# CH32V007F8U6.net
KiCad netlist of a schematic drawn in Altium Designer
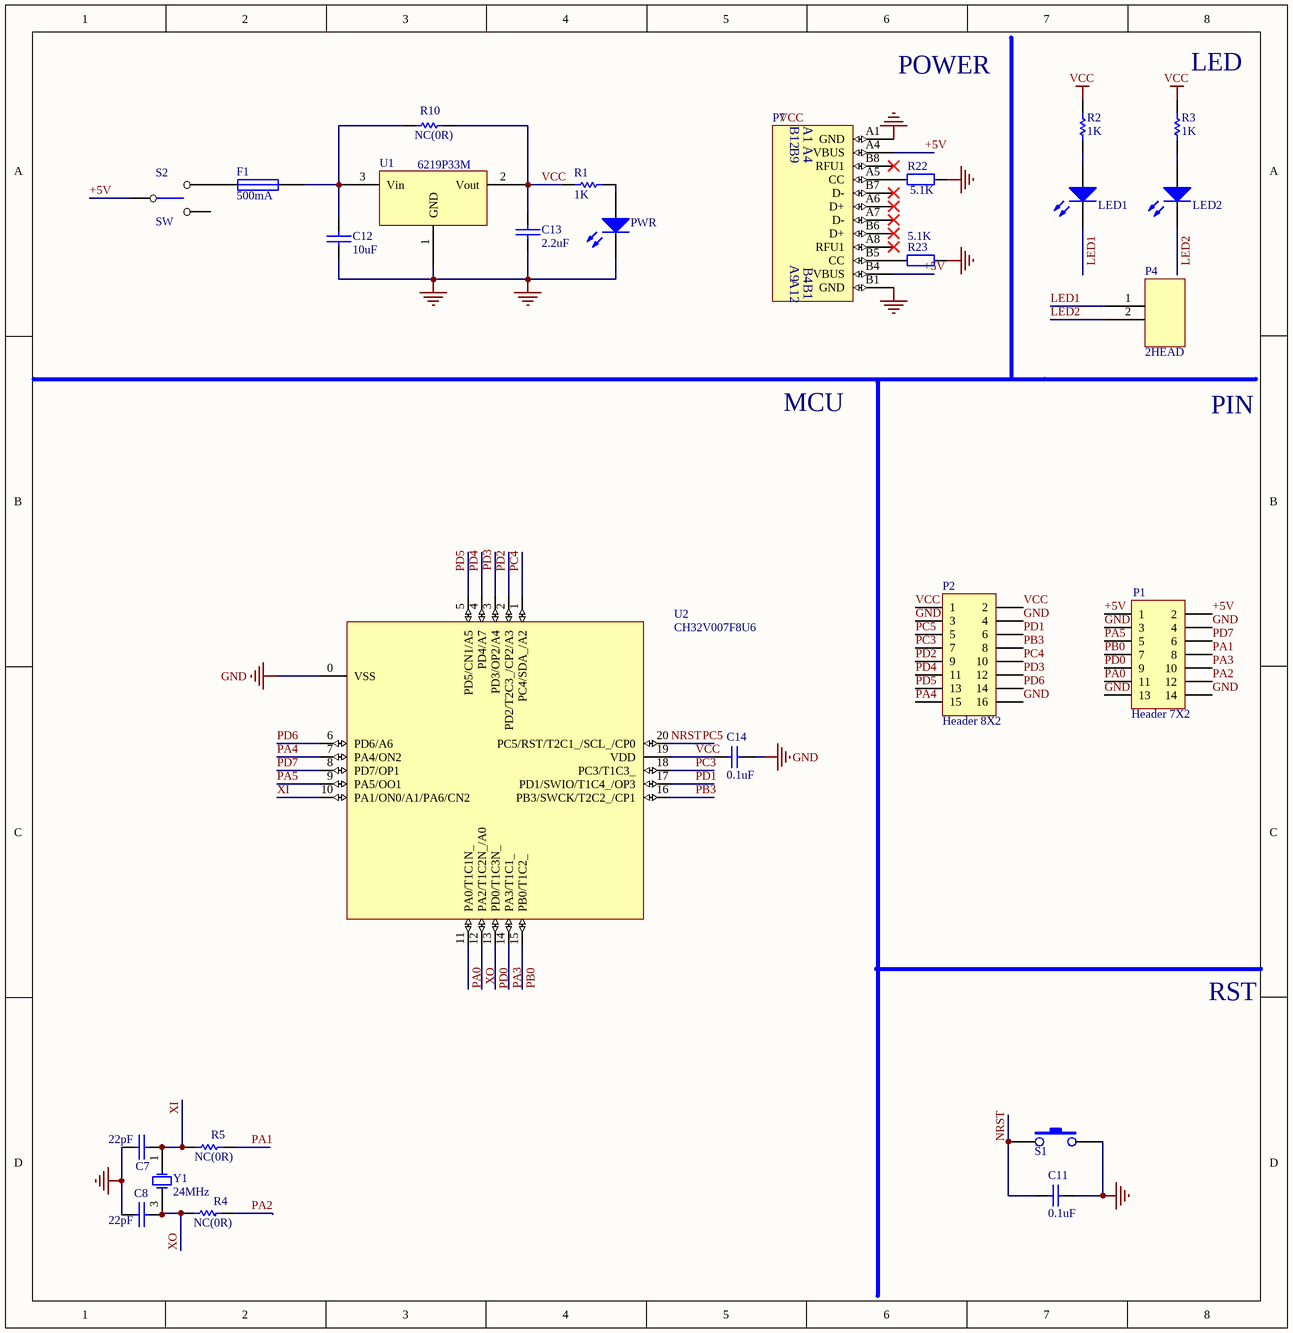
[diagram p0: CH32V007F8U6.SchDoc]

(export (version "E")
  (design (tool "Eeschema 10.0.6"))
  (components
    (comp (ref "C7")
      (value "22pF")
      (footprint "0402_C")
      (description "Capacitor")
      (libsource (lib "*") (part "CAP"))
    )
    (comp (ref "C8")
      (value "22pF")
      (footprint "0402_C")
      (description "Capacitor")
      (libsource (lib "*") (part "CAP"))
    )
    (comp (ref "C11")
      (value "0.1uF")
      (footprint "0402_C")
      (description "Capacitor")
      (fields (field (name "PUBLISHER") "Altium Limited"))
      (libsource (lib "*") (part "Cap"))
    )
    (comp (ref "C12")
      (value "10uF")
      (footprint "0603_C")
      (description "Capacitor")
      (libsource (lib "wch_sch_others") (part "CAP"))
    )
    (comp (ref "C13")
      (value "2.2uF")
      (footprint "0402_C")
      (description "Capacitor")
      (libsource (lib "wch_sch_others") (part "CAP"))
    )
    (comp (ref "C14")
      (value "0.1uF")
      (footprint "0603_C")
      (description "Capacitor")
      (fields (field (name "PUBLISHER") "Altium Limited"))
      (libsource (lib "*") (part "Cap"))
    )
    (comp (ref "F1")
      (value "500mA")
      (footprint "0603")
      (description "Fuse")
      (libsource (lib "*") (part "FUSE1"))
    )
    (comp (ref "LED1")
      (value "LED1   blue")
      (footprint "0603+")
      (description "Typical INFRARED GaAs LED")
      (fields (field (name "PUBLISHER") "Altium Limited"))
      (libsource (lib "*") (part "LED0"))
    )
    (comp (ref "LED2")
      (value "LED2  blue")
      (footprint "0603+")
      (description "Typical INFRARED GaAs LED")
      (fields (field (name "PUBLISHER") "Altium Limited"))
      (libsource (lib "*") (part "LED0"))
    )
    (comp (ref "P1")
      (value "Header 7X2")
      (footprint "HDR2X7")
      (description "Header, 7-Pin, Dual row")
      (fields (field (name "PUBLISHER") "Altium Limited"))
      (libsource (lib "Miscellaneous Connectors") (part "Header 7X2"))
    )
    (comp (ref "P2")
      (value "Header 8X2")
      (footprint "HDR2X8")
      (description "Header, 8-Pin, Dual row")
      (fields (field (name "PUBLISHER") "Altium Limited"))
      (libsource (lib "Miscellaneous Connectors") (part "Header 8X2"))
    )
    (comp (ref "P4") (value "2HEAD") (footprint "SIP2-2.54mm") (libsource (lib "*") (part "2HEAD")))
    (comp (ref "P7")
      (value "TYPE-C")
      (footprint "TYPE-C-Receptacle-2.0")
      (libsource (lib "*") (part "TYPE-C1"))
    )
    (comp (ref "PWR")
      (value "POWER  red")
      (footprint "0603+")
      (description "Typical INFRARED GaAs LED")
      (fields (field (name "PUBLISHER") "Altium Limited"))
      (libsource (lib "") (part "LED0_1"))
    )
    (comp (ref "R1")
      (value "1K")
      (footprint "0402")
      (description "Semiconductor Resistor")
      (fields (field (name "PUBLISHER") "Altium Limited"))
      (libsource (lib "*") (part "Res Semi"))
    )
    (comp (ref "R2")
      (value "1K")
      (footprint "0402")
      (description "Semiconductor Resistor")
      (fields (field (name "PUBLISHER") "Altium Limited"))
      (libsource (lib "*") (part "Res Semi"))
    )
    (comp (ref "R3")
      (value "1K")
      (footprint "0402")
      (description "Semiconductor Resistor")
      (fields (field (name "PUBLISHER") "Altium Limited"))
      (libsource (lib "*") (part "Res Semi"))
    )
    (comp (ref "R4")
      (value "NC(0R)")
      (footprint "0402")
      (description "Semiconductor Resistor")
      (fields (field (name "Comment") "0R") (field (name "PUBLISHER") "Altium Limited"))
      (libsource (lib "*") (part "Res Semi"))
    )
    (comp (ref "R5")
      (value "NC(0R)")
      (footprint "0402")
      (description "Semiconductor Resistor")
      (fields (field (name "Comment") "0R") (field (name "PUBLISHER") "Altium Limited"))
      (libsource (lib "*") (part "Res Semi"))
    )
    (comp (ref "R10")
      (value "NC(0R)")
      (footprint "0402")
      (description "Semiconductor Resistor")
      (fields (field (name "Comment") "0R") (field (name "PUBLISHER") "Altium Limited"))
      (libsource (lib "*") (part "Res Semi"))
    )
    (comp (ref "R22")
      (value "5.1K")
      (footprint "0402")
      (description "Resistor")
      (libsource (lib "Miscellaneous Devices") (part "Res2"))
    )
    (comp (ref "R23")
      (value "5.1K")
      (footprint "0402")
      (description "Resistor")
      (libsource (lib "Miscellaneous Devices") (part "Res2"))
    )
    (comp (ref "S1") (value "NRST") (footprint "SMD_6.1x3.65x2.5mm-KEY") (libsource (lib "*") (part "KEY")))
    (comp (ref "S2") (value "SW") (footprint "SW1") (libsource (lib "*") (part "SW")))
    (comp (ref "U1")
      (value "6219P33M")
      (footprint "SOT-23")
      (libsource (lib "wch_sch_others") (part "6219P33M"))
    )
    (comp (ref "U2")
      (value "CH32V007F8U6")
      (footprint "QFN20_3X3")
      (description "RISC-V MCU, ADC/OPA/CMP/2*UART/I2C/SPI")
      (libsource (lib "DHXXXSCH") (part "CH32V007F8U6"))
    )
    (comp (ref "Y1")
      (value "24MHz")
      (footprint "XT3225")
      (description "Crystal Oscillator")
      (fields (field (name "PUBLISHER") "Altium Limited"))
      (libsource (lib "*") (part "XTAL"))
    )
  )
  (nets
    (net (code "1") (name "/+5V") (class "Default")
      (node (ref "P1") (pin "1") (pinfunction "1_1") (pintype "passive"))
      (node (ref "P1") (pin "2") (pinfunction "2_2") (pintype "passive"))
      (node (ref "P7") (pin "A4") (pinfunction "VBUS_A4") (pintype "bidirectional"))
      (node (ref "P7") (pin "B4") (pinfunction "VBUS_B4") (pintype "bidirectional"))
      (node (ref "S2") (pin "1") (pinfunction "1_1") (pintype "passive"))
    )
    (net (code "2") (name "/LED1") (class "Default")
      (node (ref "LED1") (pin "2") (pinfunction "K_2") (pintype "passive"))
      (node (ref "P4") (pin "1") (pintype "passive"))
    )
    (net (code "3") (name "/LED2") (class "Default")
      (node (ref "LED2") (pin "2") (pinfunction "K_2") (pintype "passive"))
      (node (ref "P4") (pin "2") (pintype "passive"))
    )
    (net (code "4") (name "/NRST") (class "Default")
      (node (ref "C11") (pin "2") (pinfunction "2_2") (pintype "passive"))
      (node (ref "P2") (pin "5") (pinfunction "5_5") (pintype "passive"))
      (node (ref "S1") (pin "1") (pinfunction "1_1") (pintype "passive"))
      (node (ref "U2") (pin "20") (pinfunction "PC5/RST/T2C1_/SCL_/CP0_20") (pintype "bidirectional"))
    )
    (net (code "5") (name "/PA0") (class "Default")
      (node (ref "P1") (pin "11") (pinfunction "11_11") (pintype "passive"))
      (node (ref "U2") (pin "11") (pinfunction "PA0/T1C1N__11") (pintype "bidirectional"))
    )
    (net (code "6") (name "/PA1") (class "Default")
      (node (ref "P1") (pin "8") (pinfunction "8_8") (pintype "passive"))
      (node (ref "R5") (pin "2") (pinfunction "2_2") (pintype "passive"))
    )
    (net (code "7") (name "/PA2") (class "Default")
      (node (ref "P1") (pin "12") (pinfunction "12_12") (pintype "passive"))
      (node (ref "R4") (pin "2") (pinfunction "2_2") (pintype "passive"))
    )
    (net (code "8") (name "/PA3") (class "Default")
      (node (ref "P1") (pin "10") (pinfunction "10_10") (pintype "passive"))
      (node (ref "U2") (pin "14") (pinfunction "PA3/T1C1__14") (pintype "bidirectional"))
    )
    (net (code "9") (name "/PA4") (class "Default")
      (node (ref "P2") (pin "15") (pinfunction "15_15") (pintype "passive"))
      (node (ref "U2") (pin "7") (pinfunction "PA4/ON2_7") (pintype "bidirectional"))
    )
    (net (code "10") (name "/PA5") (class "Default")
      (node (ref "P1") (pin "5") (pinfunction "5_5") (pintype "passive"))
      (node (ref "U2") (pin "9") (pinfunction "PA5/OO1_9") (pintype "bidirectional"))
    )
    (net (code "11") (name "/PB0") (class "Default")
      (node (ref "P1") (pin "7") (pinfunction "7_7") (pintype "passive"))
      (node (ref "U2") (pin "15") (pinfunction "PB0/T1C2__15") (pintype "bidirectional"))
    )
    (net (code "12") (name "/PB3") (class "Default")
      (node (ref "P2") (pin "8") (pinfunction "8_8") (pintype "passive"))
      (node (ref "U2") (pin "16") (pinfunction "PB3/SWCK/T2C2_/CP1_16") (pintype "bidirectional"))
    )
    (net (code "13") (name "/PC3") (class "Default")
      (node (ref "P2") (pin "7") (pinfunction "7_7") (pintype "passive"))
      (node (ref "U2") (pin "18") (pinfunction "PC3/T1C3__18") (pintype "bidirectional"))
    )
    (net (code "14") (name "/PC4") (class "Default")
      (node (ref "P2") (pin "10") (pinfunction "10_10") (pintype "passive"))
      (node (ref "U2") (pin "1") (pinfunction "PC4/SDA_/A2_1") (pintype "bidirectional"))
    )
    (net (code "15") (name "/PD0") (class "Default")
      (node (ref "P1") (pin "9") (pinfunction "9_9") (pintype "passive"))
      (node (ref "U2") (pin "13") (pinfunction "PD0/T1C3N__13") (pintype "bidirectional"))
    )
    (net (code "16") (name "/PD1") (class "Default")
      (node (ref "P2") (pin "6") (pinfunction "6_6") (pintype "passive"))
      (node (ref "U2") (pin "17") (pinfunction "PD1/SWIO/T1C4_/OP3_17") (pintype "bidirectional"))
    )
    (net (code "17") (name "/PD2") (class "Default")
      (node (ref "P2") (pin "9") (pinfunction "9_9") (pintype "passive"))
      (node (ref "U2") (pin "2") (pinfunction "PD2/T2C3_/CP2/A3_2") (pintype "bidirectional"))
    )
    (net (code "18") (name "/PD3") (class "Default")
      (node (ref "P2") (pin "12") (pinfunction "12_12") (pintype "passive"))
      (node (ref "U2") (pin "3") (pinfunction "PD3/OP2/A4_3") (pintype "bidirectional"))
    )
    (net (code "19") (name "/PD4") (class "Default")
      (node (ref "P2") (pin "11") (pinfunction "11_11") (pintype "passive"))
      (node (ref "U2") (pin "4") (pinfunction "PD4/A7_4") (pintype "bidirectional"))
    )
    (net (code "20") (name "/PD5") (class "Default")
      (node (ref "P2") (pin "13") (pinfunction "13_13") (pintype "passive"))
      (node (ref "U2") (pin "5") (pinfunction "PD5/CN1/A5_5") (pintype "bidirectional"))
    )
    (net (code "21") (name "/PD6") (class "Default")
      (node (ref "P2") (pin "14") (pinfunction "14_14") (pintype "passive"))
      (node (ref "U2") (pin "6") (pinfunction "PD6/A6_6") (pintype "bidirectional"))
    )
    (net (code "22") (name "/PD7") (class "Default")
      (node (ref "P1") (pin "6") (pinfunction "6_6") (pintype "passive"))
      (node (ref "U2") (pin "8") (pinfunction "PD7/OP1_8") (pintype "bidirectional"))
    )
    (net (code "23") (name "/XI") (class "Default")
      (node (ref "C7") (pin "2") (pinfunction "2_2") (pintype "passive"))
      (node (ref "R5") (pin "1") (pinfunction "1_1") (pintype "passive"))
      (node (ref "U2") (pin "10") (pinfunction "PA1/ON0/A1/PA6/CN2_10") (pintype "bidirectional"))
      (node (ref "Y1") (pin "1") (pinfunction "OSC1_1") (pintype "passive"))
    )
    (net (code "24") (name "/XO") (class "Default")
      (node (ref "C8") (pin "2") (pinfunction "2_2") (pintype "passive"))
      (node (ref "R4") (pin "1") (pinfunction "1_1") (pintype "passive"))
      (node (ref "U2") (pin "12") (pinfunction "PA2/T1C2N_/A0_12") (pintype "bidirectional"))
      (node (ref "Y1") (pin "3") (pinfunction "OSC2_3") (pintype "passive"))
    )
    (net (code "25") (name "GND") (class "Default")
      (node (ref "C11") (pin "1") (pinfunction "1_1") (pintype "passive"))
      (node (ref "C12") (pin "2") (pinfunction "2_2") (pintype "passive"))
      (node (ref "C13") (pin "1") (pinfunction "1_1") (pintype "passive"))
      (node (ref "C14") (pin "2") (pinfunction "2_2") (pintype "passive"))
      (node (ref "C7") (pin "1") (pinfunction "1_1") (pintype "passive"))
      (node (ref "C8") (pin "1") (pinfunction "1_1") (pintype "passive"))
      (node (ref "P1") (pin "13") (pinfunction "13_13") (pintype "passive"))
      (node (ref "P1") (pin "14") (pinfunction "14_14") (pintype "passive"))
      (node (ref "P1") (pin "3") (pinfunction "3_3") (pintype "passive"))
      (node (ref "P1") (pin "4") (pinfunction "4_4") (pintype "passive"))
      (node (ref "P2") (pin "16") (pinfunction "16_16") (pintype "passive"))
      (node (ref "P2") (pin "3") (pinfunction "3_3") (pintype "passive"))
      (node (ref "P2") (pin "4") (pinfunction "4_4") (pintype "passive"))
      (node (ref "P7") (pin "A1") (pinfunction "GND_A1") (pintype "bidirectional"))
      (node (ref "P7") (pin "B1") (pinfunction "GND_B1") (pintype "bidirectional"))
      (node (ref "PWR") (pin "2") (pinfunction "K_2") (pintype "passive"))
      (node (ref "R22") (pin "2") (pinfunction "2_2") (pintype "passive"))
      (node (ref "R23") (pin "2") (pinfunction "2_2") (pintype "passive"))
      (node (ref "S1") (pin "2") (pinfunction "2_2") (pintype "passive"))
      (node (ref "U1") (pin "1") (pinfunction "GND_1") (pintype "passive"))
      (node (ref "U2") (pin "0") (pinfunction "VSS_0") (pintype "power_in"))
    )
    (net (code "26") (name "Net-(F1-Pad1)") (class "Default")
      (node (ref "F1") (pin "1") (pinfunction "1_1") (pintype "passive"))
      (node (ref "S2") (pin "3") (pinfunction "3_3") (pintype "passive"))
    )
    (net (code "27") (name "Net-(LED1-A)") (class "Default")
      (node (ref "LED1") (pin "1") (pinfunction "A_1") (pintype "passive"))
      (node (ref "R2") (pin "2") (pinfunction "2_2") (pintype "passive"))
    )
    (net (code "28") (name "Net-(LED2-A)") (class "Default")
      (node (ref "LED2") (pin "1") (pinfunction "A_1") (pintype "passive"))
      (node (ref "R3") (pin "2") (pinfunction "2_2") (pintype "passive"))
    )
    (net (code "29") (name "Net-(P7-CC-PadA5)") (class "Default")
      (node (ref "P7") (pin "A5") (pinfunction "CC_A5") (pintype "bidirectional"))
      (node (ref "R22") (pin "1") (pinfunction "1_1") (pintype "passive"))
    )
    (net (code "30") (name "Net-(P7-CC-PadB5)") (class "Default")
      (node (ref "P7") (pin "B5") (pinfunction "CC_B5") (pintype "bidirectional"))
      (node (ref "R23") (pin "1") (pinfunction "1_1") (pintype "passive"))
    )
    (net (code "31") (name "Net-(PWR-A)") (class "Default")
      (node (ref "PWR") (pin "1") (pinfunction "A_1") (pintype "passive"))
      (node (ref "R1") (pin "1") (pinfunction "1_1") (pintype "passive"))
    )
    (net (code "32") (name "Net-(U1-Vin)") (class "Default")
      (node (ref "C12") (pin "1") (pinfunction "1_1") (pintype "passive"))
      (node (ref "F1") (pin "2") (pinfunction "2_2") (pintype "passive"))
      (node (ref "R10") (pin "1") (pinfunction "1_1") (pintype "passive"))
      (node (ref "U1") (pin "3") (pinfunction "Vin_3") (pintype "passive"))
    )
    (net (code "33") (name "VCC") (class "Default")
      (node (ref "C13") (pin "2") (pinfunction "2_2") (pintype "passive"))
      (node (ref "C14") (pin "1") (pinfunction "1_1") (pintype "passive"))
      (node (ref "P2") (pin "1") (pinfunction "1_1") (pintype "passive"))
      (node (ref "P2") (pin "2") (pinfunction "2_2") (pintype "passive"))
      (node (ref "R1") (pin "2") (pinfunction "2_2") (pintype "passive"))
      (node (ref "R10") (pin "2") (pinfunction "2_2") (pintype "passive"))
      (node (ref "R2") (pin "1") (pinfunction "1_1") (pintype "passive"))
      (node (ref "R3") (pin "1") (pinfunction "1_1") (pintype "passive"))
      (node (ref "U1") (pin "2") (pinfunction "Vout_2") (pintype "passive"))
      (node (ref "U2") (pin "19") (pinfunction "VDD_19") (pintype "power_in"))
    )
    (net (code "34") (name "unconnected-(P7-D+-PadA6)") (class "Default")
      (node (ref "P7") (pin "A6") (pinfunction "D+_A6") (pintype "bidirectional+no_connect"))
    )
    (net (code "35") (name "unconnected-(P7-D+-PadB6)") (class "Default")
      (node (ref "P7") (pin "B6") (pinfunction "D+_B6") (pintype "bidirectional+no_connect"))
    )
    (net (code "36") (name "unconnected-(P7-D--PadA7)") (class "Default")
      (node (ref "P7") (pin "A7") (pinfunction "D-_A7") (pintype "bidirectional+no_connect"))
    )
    (net (code "37") (name "unconnected-(P7-D--PadB7)") (class "Default")
      (node (ref "P7") (pin "B7") (pinfunction "D-_B7") (pintype "bidirectional+no_connect"))
    )
    (net (code "38") (name "unconnected-(P7-RFU1-PadA8)") (class "Default")
      (node (ref "P7") (pin "A8") (pinfunction "RFU1_A8") (pintype "bidirectional+no_connect"))
    )
    (net (code "39") (name "unconnected-(P7-RFU1-PadB8)") (class "Default")
      (node (ref "P7") (pin "B8") (pinfunction "RFU1_B8") (pintype "bidirectional+no_connect"))
    )
    (net (code "40") (name "unconnected-(S2-Pad2)") (class "Default")
      (node (ref "S2") (pin "2") (pinfunction "2_2") (pintype "passive"))
    )
  )
)
